# Traffic_Light_Control_System.net
KiCad netlist of a schematic drawn in EasyEDA
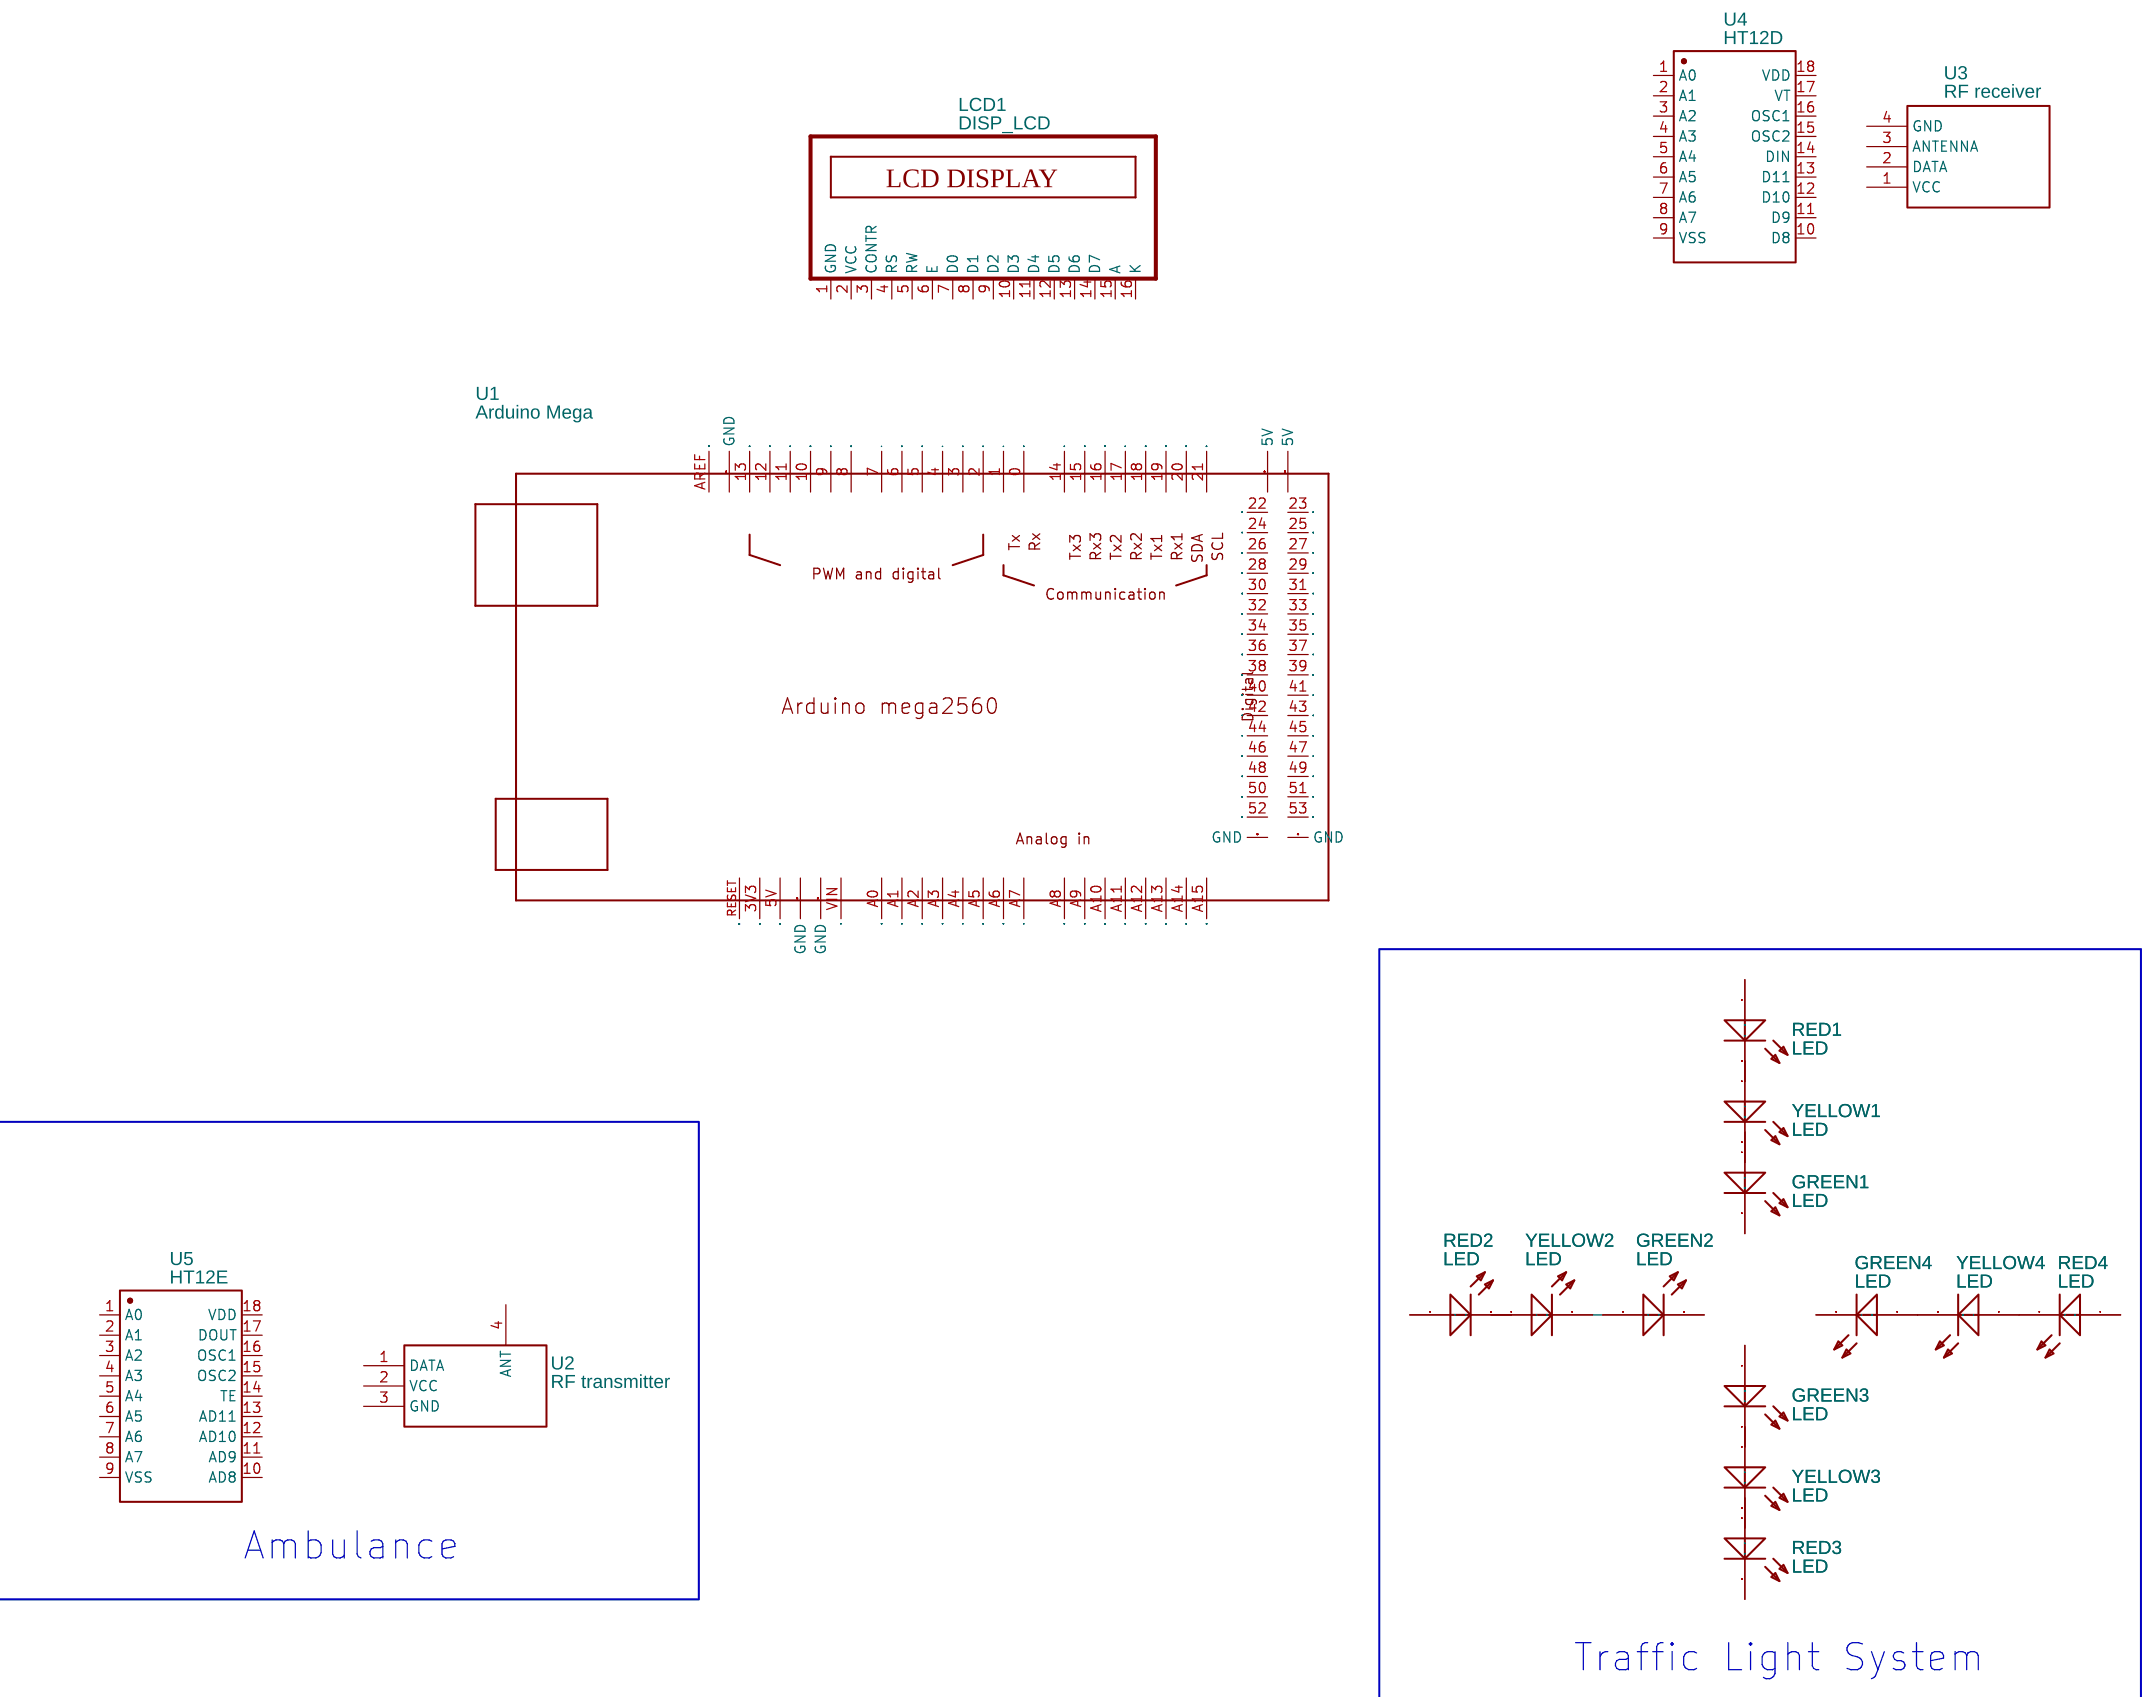
[diagram p0: schematic sheet]

(export (version "E")
  (design (tool "Eeschema 10.0.6"))
  (components
    (comp (ref "GREEN1") (value "LED") (libsource (lib "") (part "LED_3")))
    (comp (ref "GREEN2") (value "LED") (libsource (lib "") (part "LED_6")))
    (comp (ref "GREEN3") (value "LED") (libsource (lib "") (part "LED_3")))
    (comp (ref "GREEN4") (value "LED") (libsource (lib "") (part "LED_2")))
    (comp (ref "LCD1") (value "DISP_LCD") (libsource (lib "") (part "DISP_LCD")))
    (comp (ref "RED1") (value "LED") (libsource (lib "") (part "LED_4")))
    (comp (ref "RED2") (value "LED") (libsource (lib "") (part "LED")))
    (comp (ref "RED3") (value "LED") (libsource (lib "") (part "LED_4")))
    (comp (ref "RED4") (value "LED") (libsource (lib "") (part "LED_1")))
    (comp (ref "U1") (value "Arduino Mega") (libsource (lib "") (part "Arduino Mega")))
    (comp (ref "U2") (value "RF transmitter") (libsource (lib "") (part "RF transmitter")))
    (comp (ref "U3") (value "RF receiver") (libsource (lib "") (part "RF receiver")))
    (comp (ref "U4")
      (value "HT12D")
      (fields (field (name "BOM_Supplier Part") "C14360"))
      (libsource (lib "") (part "HT12D"))
    )
    (comp (ref "U5") (value "HT12E") (libsource (lib "") (part "HT12E")))
    (comp (ref "YELLOW1") (value "LED") (libsource (lib "") (part "LED_5")))
    (comp (ref "YELLOW2") (value "LED") (libsource (lib "") (part "LED_7")))
    (comp (ref "YELLOW3") (value "LED") (libsource (lib "") (part "LED_5")))
    (comp (ref "YELLOW4") (value "LED") (libsource (lib "") (part "LED_8")))
  )
  (nets
    (net (code "1") (name "Net-(GREEN2-A)") (class "Default")
      (node (ref "GREEN2") (pin "1") (pinfunction "A_1") (pintype "unspecified"))
      (node (ref "YELLOW2") (pin "2") (pinfunction "K_2") (pintype "unspecified"))
    )
    (net (code "2") (name "Net-(GREEN4-A)") (class "Default")
      (node (ref "GREEN4") (pin "1") (pinfunction "A_1") (pintype "unspecified"))
      (node (ref "YELLOW4") (pin "2") (pinfunction "K_2") (pintype "unspecified"))
    )
    (net (code "3") (name "Net-(RED1-K)") (class "Default")
      (node (ref "RED1") (pin "2") (pinfunction "K_2") (pintype "unspecified"))
      (node (ref "YELLOW1") (pin "1") (pinfunction "A_1") (pintype "unspecified"))
    )
    (net (code "4") (name "Net-(RED4-K)") (class "Default")
      (node (ref "RED4") (pin "2") (pinfunction "K_2") (pintype "unspecified"))
      (node (ref "YELLOW4") (pin "1") (pinfunction "A_1") (pintype "unspecified"))
    )
    (net (code "5") (name "unconnected-(GREEN1-A-Pad1)") (class "Default")
      (node (ref "GREEN1") (pin "1") (pinfunction "A_1") (pintype "unspecified"))
    )
    (net (code "6") (name "unconnected-(GREEN1-K-Pad2)") (class "Default")
      (node (ref "GREEN1") (pin "2") (pinfunction "K_2") (pintype "unspecified"))
    )
    (net (code "7") (name "unconnected-(GREEN2-K-Pad2)") (class "Default")
      (node (ref "GREEN2") (pin "2") (pinfunction "K_2") (pintype "unspecified"))
    )
    (net (code "8") (name "unconnected-(GREEN3-A-Pad1)") (class "Default")
      (node (ref "GREEN3") (pin "1") (pinfunction "A_1") (pintype "unspecified"))
    )
    (net (code "9") (name "unconnected-(GREEN3-K-Pad2)") (class "Default")
      (node (ref "GREEN3") (pin "2") (pinfunction "K_2") (pintype "unspecified"))
    )
    (net (code "10") (name "unconnected-(GREEN4-K-Pad2)") (class "Default")
      (node (ref "GREEN4") (pin "2") (pinfunction "K_2") (pintype "unspecified"))
    )
    (net (code "11") (name "unconnected-(LCD1-A-Pad15)") (class "Default")
      (node (ref "LCD1") (pin "15") (pinfunction "A_15") (pintype "unspecified"))
    )
    (net (code "12") (name "unconnected-(LCD1-CONTR-Pad3)") (class "Default")
      (node (ref "LCD1") (pin "3") (pinfunction "CONTR_3") (pintype "input"))
    )
    (net (code "13") (name "unconnected-(LCD1-D0-Pad7)") (class "Default")
      (node (ref "LCD1") (pin "7") (pinfunction "D0_7") (pintype "input"))
    )
    (net (code "14") (name "unconnected-(LCD1-D1-Pad8)") (class "Default")
      (node (ref "LCD1") (pin "8") (pinfunction "D1_8") (pintype "input"))
    )
    (net (code "15") (name "unconnected-(LCD1-D2-Pad9)") (class "Default")
      (node (ref "LCD1") (pin "9") (pinfunction "D2_9") (pintype "input"))
    )
    (net (code "16") (name "unconnected-(LCD1-D3-Pad10)") (class "Default")
      (node (ref "LCD1") (pin "10") (pinfunction "D3_10") (pintype "input"))
    )
    (net (code "17") (name "unconnected-(LCD1-D4-Pad11)") (class "Default")
      (node (ref "LCD1") (pin "11") (pinfunction "D4_11") (pintype "input"))
    )
    (net (code "18") (name "unconnected-(LCD1-D5-Pad12)") (class "Default")
      (node (ref "LCD1") (pin "12") (pinfunction "D5_12") (pintype "input"))
    )
    (net (code "19") (name "unconnected-(LCD1-D6-Pad13)") (class "Default")
      (node (ref "LCD1") (pin "13") (pinfunction "D6_13") (pintype "input"))
    )
    (net (code "20") (name "unconnected-(LCD1-D7-Pad14)") (class "Default")
      (node (ref "LCD1") (pin "14") (pinfunction "D7_14") (pintype "input"))
    )
    (net (code "21") (name "unconnected-(LCD1-E-Pad6)") (class "Default")
      (node (ref "LCD1") (pin "6") (pinfunction "E_6") (pintype "input"))
    )
    (net (code "22") (name "unconnected-(LCD1-GND-Pad1)") (class "Default")
      (node (ref "LCD1") (pin "1") (pinfunction "GND_1") (pintype "unspecified"))
    )
    (net (code "23") (name "unconnected-(LCD1-K-Pad16)") (class "Default")
      (node (ref "LCD1") (pin "16") (pinfunction "K_16") (pintype "unspecified"))
    )
    (net (code "24") (name "unconnected-(LCD1-RS-Pad4)") (class "Default")
      (node (ref "LCD1") (pin "4") (pinfunction "RS_4") (pintype "input"))
    )
    (net (code "25") (name "unconnected-(LCD1-RW-Pad5)") (class "Default")
      (node (ref "LCD1") (pin "5") (pinfunction "RW_5") (pintype "input"))
    )
    (net (code "26") (name "unconnected-(LCD1-VCC-Pad2)") (class "Default")
      (node (ref "LCD1") (pin "2") (pinfunction "VCC_2") (pintype "unspecified"))
    )
    (net (code "27") (name "unconnected-(RED1-A-Pad1)") (class "Default")
      (node (ref "RED1") (pin "1") (pinfunction "A_1") (pintype "unspecified"))
    )
    (net (code "28") (name "unconnected-(RED2-A-Pad1)") (class "Default")
      (node (ref "RED2") (pin "1") (pinfunction "A_1") (pintype "unspecified"))
    )
    (net (code "29") (name "unconnected-(RED2-K-Pad2)") (class "Default")
      (node (ref "RED2") (pin "2") (pinfunction "K_2") (pintype "unspecified"))
    )
    (net (code "30") (name "unconnected-(RED3-A-Pad1)") (class "Default")
      (node (ref "RED3") (pin "1") (pinfunction "A_1") (pintype "unspecified"))
    )
    (net (code "31") (name "unconnected-(RED3-K-Pad2)") (class "Default")
      (node (ref "RED3") (pin "2") (pinfunction "K_2") (pintype "unspecified"))
    )
    (net (code "32") (name "unconnected-(RED4-A-Pad1)") (class "Default")
      (node (ref "RED4") (pin "1") (pinfunction "A_1") (pintype "unspecified"))
    )
    (net (code "33") (name "unconnected-(U1-5V-PadGND@4)") (class "Default")
      (node (ref "U1") (pin "GND@4") (pinfunction "5V_GND@4") (pintype "unspecified"))
    )
    (net (code "34") (name "unconnected-(U1-5V-PadGND@5)") (class "Default")
      (node (ref "U1") (pin "GND@5") (pinfunction "5V_GND@5") (pintype "unspecified"))
    )
    (net (code "35") (name "unconnected-(U1-GND-PadGND@1)") (class "Default")
      (node (ref "U1") (pin "GND@1") (pinfunction "GND_GND@1") (pintype "unspecified"))
    )
    (net (code "36") (name "unconnected-(U1-GND-PadGND@2)") (class "Default")
      (node (ref "U1") (pin "GND@2") (pinfunction "GND_GND@2") (pintype "unspecified"))
    )
    (net (code "37") (name "unconnected-(U1-GND-PadGND@3)") (class "Default")
      (node (ref "U1") (pin "GND@3") (pinfunction "GND_GND@3") (pintype "unspecified"))
    )
    (net (code "38") (name "unconnected-(U1-GND-PadGND@6)") (class "Default")
      (node (ref "U1") (pin "GND@6") (pinfunction "GND_GND@6") (pintype "unspecified"))
    )
    (net (code "39") (name "unconnected-(U1-GND-PadGND@7)") (class "Default")
      (node (ref "U1") (pin "GND@7") (pinfunction "GND_GND@7") (pintype "unspecified"))
    )
    (net (code "40") (name "unconnected-(U1-Pad0)") (class "Default")
      (node (ref "U1") (pin "0") (pinfunction "0_0") (pintype "unspecified"))
    )
    (net (code "41") (name "unconnected-(U1-Pad1)") (class "Default")
      (node (ref "U1") (pin "1") (pinfunction "1_1") (pintype "unspecified"))
    )
    (net (code "42") (name "unconnected-(U1-Pad2)") (class "Default")
      (node (ref "U1") (pin "2") (pinfunction "2_2") (pintype "unspecified"))
    )
    (net (code "43") (name "unconnected-(U1-Pad3)") (class "Default")
      (node (ref "U1") (pin "3") (pinfunction "3_3") (pintype "unspecified"))
    )
    (net (code "44") (name "unconnected-(U1-Pad3V3)") (class "Default")
      (node (ref "U1") (pin "3V3") (pinfunction "3V3_3V3") (pintype "unspecified"))
    )
    (net (code "45") (name "unconnected-(U1-Pad4)") (class "Default")
      (node (ref "U1") (pin "4") (pinfunction "4_4") (pintype "unspecified"))
    )
    (net (code "46") (name "unconnected-(U1-Pad5)") (class "Default")
      (node (ref "U1") (pin "5") (pinfunction "5_5") (pintype "unspecified"))
    )
    (net (code "47") (name "unconnected-(U1-Pad5V)") (class "Default")
      (node (ref "U1") (pin "5V") (pinfunction "5V_5V") (pintype "unspecified"))
    )
    (net (code "48") (name "unconnected-(U1-Pad6)") (class "Default")
      (node (ref "U1") (pin "6") (pinfunction "6_6") (pintype "unspecified"))
    )
    (net (code "49") (name "unconnected-(U1-Pad7)") (class "Default")
      (node (ref "U1") (pin "7") (pinfunction "7_7") (pintype "unspecified"))
    )
    (net (code "50") (name "unconnected-(U1-Pad8)") (class "Default")
      (node (ref "U1") (pin "8") (pinfunction "8_8") (pintype "unspecified"))
    )
    (net (code "51") (name "unconnected-(U1-Pad9)") (class "Default")
      (node (ref "U1") (pin "9") (pinfunction "9_9") (pintype "unspecified"))
    )
    (net (code "52") (name "unconnected-(U1-Pad10)") (class "Default")
      (node (ref "U1") (pin "10") (pinfunction "10_10") (pintype "unspecified"))
    )
    (net (code "53") (name "unconnected-(U1-Pad11)") (class "Default")
      (node (ref "U1") (pin "11") (pinfunction "11_11") (pintype "unspecified"))
    )
    (net (code "54") (name "unconnected-(U1-Pad12)") (class "Default")
      (node (ref "U1") (pin "12") (pinfunction "12_12") (pintype "unspecified"))
    )
    (net (code "55") (name "unconnected-(U1-Pad13)") (class "Default")
      (node (ref "U1") (pin "13") (pinfunction "13_13") (pintype "unspecified"))
    )
    (net (code "56") (name "unconnected-(U1-Pad14)") (class "Default")
      (node (ref "U1") (pin "14") (pinfunction "14_14") (pintype "unspecified"))
    )
    (net (code "57") (name "unconnected-(U1-Pad15)") (class "Default")
      (node (ref "U1") (pin "15") (pinfunction "15_15") (pintype "unspecified"))
    )
    (net (code "58") (name "unconnected-(U1-Pad16)") (class "Default")
      (node (ref "U1") (pin "16") (pinfunction "16_16") (pintype "unspecified"))
    )
    (net (code "59") (name "unconnected-(U1-Pad17)") (class "Default")
      (node (ref "U1") (pin "17") (pinfunction "17_17") (pintype "unspecified"))
    )
    (net (code "60") (name "unconnected-(U1-Pad18)") (class "Default")
      (node (ref "U1") (pin "18") (pinfunction "18_18") (pintype "unspecified"))
    )
    (net (code "61") (name "unconnected-(U1-Pad19)") (class "Default")
      (node (ref "U1") (pin "19") (pinfunction "19_19") (pintype "unspecified"))
    )
    (net (code "62") (name "unconnected-(U1-Pad20)") (class "Default")
      (node (ref "U1") (pin "20") (pinfunction "20_20") (pintype "unspecified"))
    )
    (net (code "63") (name "unconnected-(U1-Pad21)") (class "Default")
      (node (ref "U1") (pin "21") (pinfunction "21_21") (pintype "unspecified"))
    )
    (net (code "64") (name "unconnected-(U1-Pad22)") (class "Default")
      (node (ref "U1") (pin "22") (pinfunction "22_22") (pintype "unspecified"))
    )
    (net (code "65") (name "unconnected-(U1-Pad23)") (class "Default")
      (node (ref "U1") (pin "23") (pinfunction "23_23") (pintype "unspecified"))
    )
    (net (code "66") (name "unconnected-(U1-Pad24)") (class "Default")
      (node (ref "U1") (pin "24") (pinfunction "24_24") (pintype "unspecified"))
    )
    (net (code "67") (name "unconnected-(U1-Pad25)") (class "Default")
      (node (ref "U1") (pin "25") (pinfunction "25_25") (pintype "unspecified"))
    )
    (net (code "68") (name "unconnected-(U1-Pad26)") (class "Default")
      (node (ref "U1") (pin "26") (pinfunction "26_26") (pintype "unspecified"))
    )
    (net (code "69") (name "unconnected-(U1-Pad27)") (class "Default")
      (node (ref "U1") (pin "27") (pinfunction "27_27") (pintype "unspecified"))
    )
    (net (code "70") (name "unconnected-(U1-Pad28)") (class "Default")
      (node (ref "U1") (pin "28") (pinfunction "28_28") (pintype "unspecified"))
    )
    (net (code "71") (name "unconnected-(U1-Pad29)") (class "Default")
      (node (ref "U1") (pin "29") (pinfunction "29_29") (pintype "unspecified"))
    )
    (net (code "72") (name "unconnected-(U1-Pad30)") (class "Default")
      (node (ref "U1") (pin "30") (pinfunction "30_30") (pintype "unspecified"))
    )
    (net (code "73") (name "unconnected-(U1-Pad31)") (class "Default")
      (node (ref "U1") (pin "31") (pinfunction "31_31") (pintype "unspecified"))
    )
    (net (code "74") (name "unconnected-(U1-Pad32)") (class "Default")
      (node (ref "U1") (pin "32") (pinfunction "32_32") (pintype "unspecified"))
    )
    (net (code "75") (name "unconnected-(U1-Pad33)") (class "Default")
      (node (ref "U1") (pin "33") (pinfunction "33_33") (pintype "unspecified"))
    )
    (net (code "76") (name "unconnected-(U1-Pad34)") (class "Default")
      (node (ref "U1") (pin "34") (pinfunction "34_34") (pintype "unspecified"))
    )
    (net (code "77") (name "unconnected-(U1-Pad35)") (class "Default")
      (node (ref "U1") (pin "35") (pinfunction "35_35") (pintype "unspecified"))
    )
    (net (code "78") (name "unconnected-(U1-Pad36)") (class "Default")
      (node (ref "U1") (pin "36") (pinfunction "36_36") (pintype "unspecified"))
    )
    (net (code "79") (name "unconnected-(U1-Pad37)") (class "Default")
      (node (ref "U1") (pin "37") (pinfunction "37_37") (pintype "unspecified"))
    )
    (net (code "80") (name "unconnected-(U1-Pad38)") (class "Default")
      (node (ref "U1") (pin "38") (pinfunction "38_38") (pintype "unspecified"))
    )
    (net (code "81") (name "unconnected-(U1-Pad39)") (class "Default")
      (node (ref "U1") (pin "39") (pinfunction "39_39") (pintype "unspecified"))
    )
    (net (code "82") (name "unconnected-(U1-Pad40)") (class "Default")
      (node (ref "U1") (pin "40") (pinfunction "40_40") (pintype "unspecified"))
    )
    (net (code "83") (name "unconnected-(U1-Pad41)") (class "Default")
      (node (ref "U1") (pin "41") (pinfunction "41_41") (pintype "unspecified"))
    )
    (net (code "84") (name "unconnected-(U1-Pad42)") (class "Default")
      (node (ref "U1") (pin "42") (pinfunction "42_42") (pintype "unspecified"))
    )
    (net (code "85") (name "unconnected-(U1-Pad43)") (class "Default")
      (node (ref "U1") (pin "43") (pinfunction "43_43") (pintype "unspecified"))
    )
    (net (code "86") (name "unconnected-(U1-Pad44)") (class "Default")
      (node (ref "U1") (pin "44") (pinfunction "44_44") (pintype "unspecified"))
    )
    (net (code "87") (name "unconnected-(U1-Pad45)") (class "Default")
      (node (ref "U1") (pin "45") (pinfunction "45_45") (pintype "unspecified"))
    )
    (net (code "88") (name "unconnected-(U1-Pad46)") (class "Default")
      (node (ref "U1") (pin "46") (pinfunction "46_46") (pintype "unspecified"))
    )
    (net (code "89") (name "unconnected-(U1-Pad47)") (class "Default")
      (node (ref "U1") (pin "47") (pinfunction "47_47") (pintype "unspecified"))
    )
    (net (code "90") (name "unconnected-(U1-Pad48)") (class "Default")
      (node (ref "U1") (pin "48") (pinfunction "48_48") (pintype "unspecified"))
    )
    (net (code "91") (name "unconnected-(U1-Pad49)") (class "Default")
      (node (ref "U1") (pin "49") (pinfunction "49_49") (pintype "unspecified"))
    )
    (net (code "92") (name "unconnected-(U1-Pad50)") (class "Default")
      (node (ref "U1") (pin "50") (pinfunction "50_50") (pintype "unspecified"))
    )
    (net (code "93") (name "unconnected-(U1-Pad51)") (class "Default")
      (node (ref "U1") (pin "51") (pinfunction "51_51") (pintype "unspecified"))
    )
    (net (code "94") (name "unconnected-(U1-Pad52)") (class "Default")
      (node (ref "U1") (pin "52") (pinfunction "52_52") (pintype "unspecified"))
    )
    (net (code "95") (name "unconnected-(U1-Pad53)") (class "Default")
      (node (ref "U1") (pin "53") (pinfunction "53_53") (pintype "unspecified"))
    )
    (net (code "96") (name "unconnected-(U1-PadA0)") (class "Default")
      (node (ref "U1") (pin "A0") (pinfunction "A0_A0") (pintype "unspecified"))
    )
    (net (code "97") (name "unconnected-(U1-PadA1)") (class "Default")
      (node (ref "U1") (pin "A1") (pinfunction "A1_A1") (pintype "unspecified"))
    )
    (net (code "98") (name "unconnected-(U1-PadA2)") (class "Default")
      (node (ref "U1") (pin "A2") (pinfunction "A2_A2") (pintype "unspecified"))
    )
    (net (code "99") (name "unconnected-(U1-PadA3)") (class "Default")
      (node (ref "U1") (pin "A3") (pinfunction "A3_A3") (pintype "unspecified"))
    )
    (net (code "100") (name "unconnected-(U1-PadA4)") (class "Default")
      (node (ref "U1") (pin "A4") (pinfunction "A4_A4") (pintype "unspecified"))
    )
    (net (code "101") (name "unconnected-(U1-PadA5)") (class "Default")
      (node (ref "U1") (pin "A5") (pinfunction "A5_A5") (pintype "unspecified"))
    )
    (net (code "102") (name "unconnected-(U1-PadA6)") (class "Default")
      (node (ref "U1") (pin "A6") (pinfunction "A6_A6") (pintype "unspecified"))
    )
    (net (code "103") (name "unconnected-(U1-PadA7)") (class "Default")
      (node (ref "U1") (pin "A7") (pinfunction "A7_A7") (pintype "unspecified"))
    )
    (net (code "104") (name "unconnected-(U1-PadA8)") (class "Default")
      (node (ref "U1") (pin "A8") (pinfunction "A8_A8") (pintype "unspecified"))
    )
    (net (code "105") (name "unconnected-(U1-PadA9)") (class "Default")
      (node (ref "U1") (pin "A9") (pinfunction "A9_A9") (pintype "unspecified"))
    )
    (net (code "106") (name "unconnected-(U1-PadA10)") (class "Default")
      (node (ref "U1") (pin "A10") (pinfunction "A10_A10") (pintype "unspecified"))
    )
    (net (code "107") (name "unconnected-(U1-PadA11)") (class "Default")
      (node (ref "U1") (pin "A11") (pinfunction "A11_A11") (pintype "unspecified"))
    )
    (net (code "108") (name "unconnected-(U1-PadA12)") (class "Default")
      (node (ref "U1") (pin "A12") (pinfunction "A12_A12") (pintype "unspecified"))
    )
    (net (code "109") (name "unconnected-(U1-PadA13)") (class "Default")
      (node (ref "U1") (pin "A13") (pinfunction "A13_A13") (pintype "unspecified"))
    )
    (net (code "110") (name "unconnected-(U1-PadA14)") (class "Default")
      (node (ref "U1") (pin "A14") (pinfunction "A14_A14") (pintype "unspecified"))
    )
    (net (code "111") (name "unconnected-(U1-PadA15)") (class "Default")
      (node (ref "U1") (pin "A15") (pinfunction "A15_A15") (pintype "unspecified"))
    )
    (net (code "112") (name "unconnected-(U1-PadAREF)") (class "Default")
      (node (ref "U1") (pin "AREF") (pinfunction "AREF_AREF") (pintype "unspecified"))
    )
    (net (code "113") (name "unconnected-(U1-PadRESET)") (class "Default")
      (node (ref "U1") (pin "RESET") (pinfunction "RESET_RESET") (pintype "unspecified"))
    )
    (net (code "114") (name "unconnected-(U1-PadVIN)") (class "Default")
      (node (ref "U1") (pin "VIN") (pinfunction "VIN_VIN") (pintype "unspecified"))
    )
    (net (code "115") (name "unconnected-(U2-ANT-Pad4)") (class "Default")
      (node (ref "U2") (pin "4") (pinfunction "ANT_4") (pintype "unspecified"))
    )
    (net (code "116") (name "unconnected-(U2-DATA-Pad1)") (class "Default")
      (node (ref "U2") (pin "1") (pinfunction "DATA_1") (pintype "unspecified"))
    )
    (net (code "117") (name "unconnected-(U2-GND-Pad3)") (class "Default")
      (node (ref "U2") (pin "3") (pinfunction "GND_3") (pintype "unspecified"))
    )
    (net (code "118") (name "unconnected-(U2-VCC-Pad2)") (class "Default")
      (node (ref "U2") (pin "2") (pinfunction "VCC_2") (pintype "unspecified"))
    )
    (net (code "119") (name "unconnected-(U3-ANTENNA-Pad3)") (class "Default")
      (node (ref "U3") (pin "3") (pinfunction "ANTENNA_3") (pintype "unspecified"))
    )
    (net (code "120") (name "unconnected-(U3-DATA-Pad2)") (class "Default")
      (node (ref "U3") (pin "2") (pinfunction "DATA_2") (pintype "unspecified"))
    )
    (net (code "121") (name "unconnected-(U3-GND-Pad4)") (class "Default")
      (node (ref "U3") (pin "4") (pinfunction "GND_4") (pintype "unspecified"))
    )
    (net (code "122") (name "unconnected-(U3-VCC-Pad1)") (class "Default")
      (node (ref "U3") (pin "1") (pinfunction "VCC_1") (pintype "unspecified"))
    )
    (net (code "123") (name "unconnected-(U4-A0-Pad1)") (class "Default")
      (node (ref "U4") (pin "1") (pinfunction "A0_1") (pintype "unspecified"))
    )
    (net (code "124") (name "unconnected-(U4-A1-Pad2)") (class "Default")
      (node (ref "U4") (pin "2") (pinfunction "A1_2") (pintype "unspecified"))
    )
    (net (code "125") (name "unconnected-(U4-A2-Pad3)") (class "Default")
      (node (ref "U4") (pin "3") (pinfunction "A2_3") (pintype "unspecified"))
    )
    (net (code "126") (name "unconnected-(U4-A3-Pad4)") (class "Default")
      (node (ref "U4") (pin "4") (pinfunction "A3_4") (pintype "unspecified"))
    )
    (net (code "127") (name "unconnected-(U4-A4-Pad5)") (class "Default")
      (node (ref "U4") (pin "5") (pinfunction "A4_5") (pintype "unspecified"))
    )
    (net (code "128") (name "unconnected-(U4-A5-Pad6)") (class "Default")
      (node (ref "U4") (pin "6") (pinfunction "A5_6") (pintype "unspecified"))
    )
    (net (code "129") (name "unconnected-(U4-A6-Pad7)") (class "Default")
      (node (ref "U4") (pin "7") (pinfunction "A6_7") (pintype "unspecified"))
    )
    (net (code "130") (name "unconnected-(U4-A7-Pad8)") (class "Default")
      (node (ref "U4") (pin "8") (pinfunction "A7_8") (pintype "unspecified"))
    )
    (net (code "131") (name "unconnected-(U4-D8-Pad10)") (class "Default")
      (node (ref "U4") (pin "10") (pinfunction "D8_10") (pintype "unspecified"))
    )
    (net (code "132") (name "unconnected-(U4-D9-Pad11)") (class "Default")
      (node (ref "U4") (pin "11") (pinfunction "D9_11") (pintype "unspecified"))
    )
    (net (code "133") (name "unconnected-(U4-D10-Pad12)") (class "Default")
      (node (ref "U4") (pin "12") (pinfunction "D10_12") (pintype "unspecified"))
    )
    (net (code "134") (name "unconnected-(U4-D11-Pad13)") (class "Default")
      (node (ref "U4") (pin "13") (pinfunction "D11_13") (pintype "unspecified"))
    )
    (net (code "135") (name "unconnected-(U4-DIN-Pad14)") (class "Default")
      (node (ref "U4") (pin "14") (pinfunction "DIN_14") (pintype "unspecified"))
    )
    (net (code "136") (name "unconnected-(U4-OSC1-Pad16)") (class "Default")
      (node (ref "U4") (pin "16") (pinfunction "OSC1_16") (pintype "unspecified"))
    )
    (net (code "137") (name "unconnected-(U4-OSC2-Pad15)") (class "Default")
      (node (ref "U4") (pin "15") (pinfunction "OSC2_15") (pintype "unspecified"))
    )
    (net (code "138") (name "unconnected-(U4-VDD-Pad18)") (class "Default")
      (node (ref "U4") (pin "18") (pinfunction "VDD_18") (pintype "unspecified"))
    )
    (net (code "139") (name "unconnected-(U4-VSS-Pad9)") (class "Default")
      (node (ref "U4") (pin "9") (pinfunction "VSS_9") (pintype "unspecified"))
    )
    (net (code "140") (name "unconnected-(U4-VT-Pad17)") (class "Default")
      (node (ref "U4") (pin "17") (pinfunction "VT_17") (pintype "unspecified"))
    )
    (net (code "141") (name "unconnected-(U5-A0-Pad1)") (class "Default")
      (node (ref "U5") (pin "1") (pinfunction "A0_1") (pintype "unspecified"))
    )
    (net (code "142") (name "unconnected-(U5-A1-Pad2)") (class "Default")
      (node (ref "U5") (pin "2") (pinfunction "A1_2") (pintype "unspecified"))
    )
    (net (code "143") (name "unconnected-(U5-A2-Pad3)") (class "Default")
      (node (ref "U5") (pin "3") (pinfunction "A2_3") (pintype "unspecified"))
    )
    (net (code "144") (name "unconnected-(U5-A3-Pad4)") (class "Default")
      (node (ref "U5") (pin "4") (pinfunction "A3_4") (pintype "unspecified"))
    )
    (net (code "145") (name "unconnected-(U5-A4-Pad5)") (class "Default")
      (node (ref "U5") (pin "5") (pinfunction "A4_5") (pintype "unspecified"))
    )
    (net (code "146") (name "unconnected-(U5-A5-Pad6)") (class "Default")
      (node (ref "U5") (pin "6") (pinfunction "A5_6") (pintype "unspecified"))
    )
    (net (code "147") (name "unconnected-(U5-A6-Pad7)") (class "Default")
      (node (ref "U5") (pin "7") (pinfunction "A6_7") (pintype "unspecified"))
    )
    (net (code "148") (name "unconnected-(U5-A7-Pad8)") (class "Default")
      (node (ref "U5") (pin "8") (pinfunction "A7_8") (pintype "unspecified"))
    )
    (net (code "149") (name "unconnected-(U5-AD8-Pad10)") (class "Default")
      (node (ref "U5") (pin "10") (pinfunction "AD8_10") (pintype "unspecified"))
    )
    (net (code "150") (name "unconnected-(U5-AD9-Pad11)") (class "Default")
      (node (ref "U5") (pin "11") (pinfunction "AD9_11") (pintype "unspecified"))
    )
    (net (code "151") (name "unconnected-(U5-AD10-Pad12)") (class "Default")
      (node (ref "U5") (pin "12") (pinfunction "AD10_12") (pintype "unspecified"))
    )
    (net (code "152") (name "unconnected-(U5-AD11-Pad13)") (class "Default")
      (node (ref "U5") (pin "13") (pinfunction "AD11_13") (pintype "unspecified"))
    )
    (net (code "153") (name "unconnected-(U5-DOUT-Pad17)") (class "Default")
      (node (ref "U5") (pin "17") (pinfunction "DOUT_17") (pintype "unspecified"))
    )
    (net (code "154") (name "unconnected-(U5-OSC1-Pad16)") (class "Default")
      (node (ref "U5") (pin "16") (pinfunction "OSC1_16") (pintype "unspecified"))
    )
    (net (code "155") (name "unconnected-(U5-OSC2-Pad15)") (class "Default")
      (node (ref "U5") (pin "15") (pinfunction "OSC2_15") (pintype "unspecified"))
    )
    (net (code "156") (name "unconnected-(U5-TE-Pad14)") (class "Default")
      (node (ref "U5") (pin "14") (pinfunction "TE_14") (pintype "unspecified"))
    )
    (net (code "157") (name "unconnected-(U5-VDD-Pad18)") (class "Default")
      (node (ref "U5") (pin "18") (pinfunction "VDD_18") (pintype "unspecified"))
    )
    (net (code "158") (name "unconnected-(U5-VSS-Pad9)") (class "Default")
      (node (ref "U5") (pin "9") (pinfunction "VSS_9") (pintype "unspecified"))
    )
    (net (code "159") (name "unconnected-(YELLOW1-K-Pad2)") (class "Default")
      (node (ref "YELLOW1") (pin "2") (pinfunction "K_2") (pintype "unspecified"))
    )
    (net (code "160") (name "unconnected-(YELLOW2-A-Pad1)") (class "Default")
      (node (ref "YELLOW2") (pin "1") (pinfunction "A_1") (pintype "unspecified"))
    )
    (net (code "161") (name "unconnected-(YELLOW3-A-Pad1)") (class "Default")
      (node (ref "YELLOW3") (pin "1") (pinfunction "A_1") (pintype "unspecified"))
    )
    (net (code "162") (name "unconnected-(YELLOW3-K-Pad2)") (class "Default")
      (node (ref "YELLOW3") (pin "2") (pinfunction "K_2") (pintype "unspecified"))
    )
  )
)
